# ButtonBoard.net
KiCad netlist of a schematic drawn in EAGLE
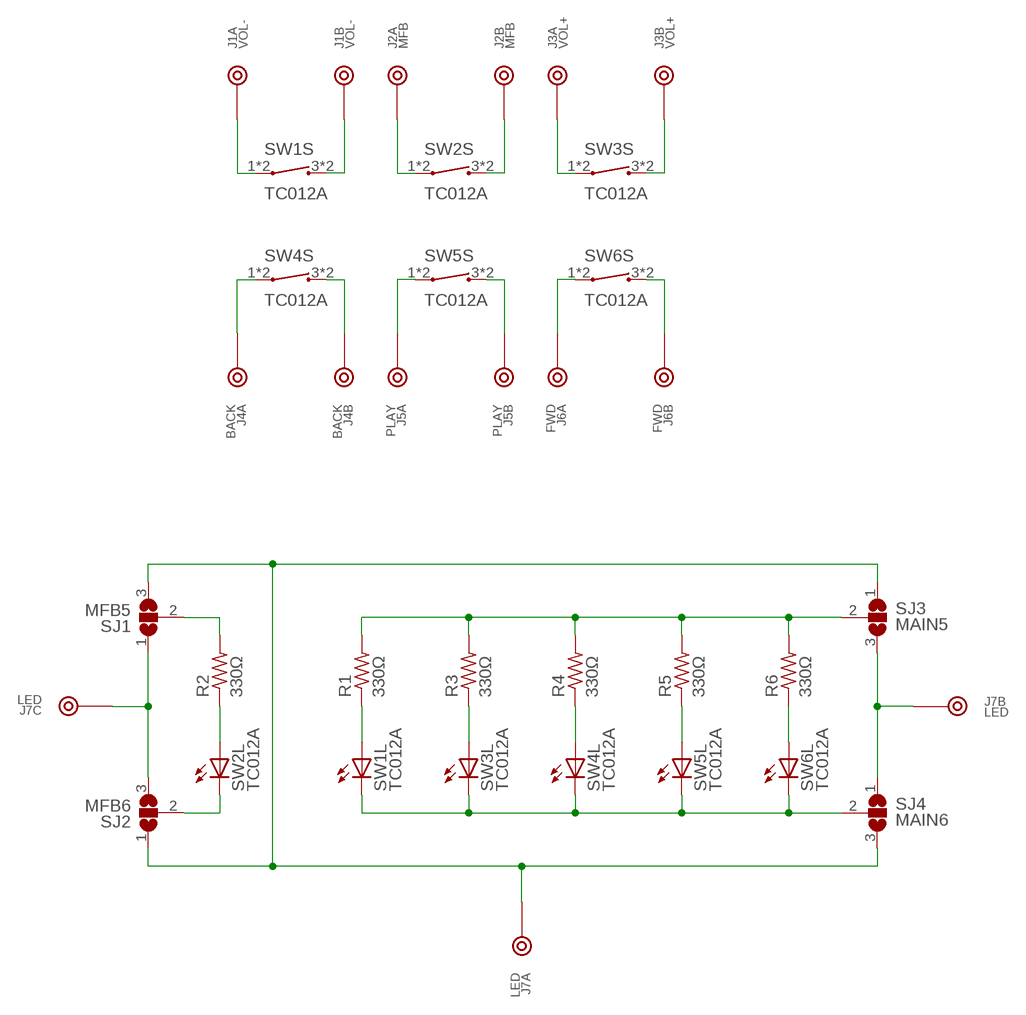
[diagram p0: schematic, sheet 1]

(export (version "E")
  (design (tool "Eeschema 10.0.6"))
  (components
    (comp (ref "J1")
      (value "VOL-")
      (footprint "eagle-import:2PIN")
      (libsource (lib "eagle-import") (part "GEN-2PIN"))
    )
    (comp (ref "J2")
      (value "MFB")
      (footprint "eagle-import:2PIN")
      (libsource (lib "eagle-import") (part "GEN-2PIN"))
    )
    (comp (ref "J3")
      (value "VOL+")
      (footprint "eagle-import:2PIN")
      (libsource (lib "eagle-import") (part "GEN-2PIN"))
    )
    (comp (ref "J4")
      (value "BACK")
      (footprint "eagle-import:2PIN")
      (libsource (lib "eagle-import") (part "GEN-2PIN"))
    )
    (comp (ref "J5")
      (value "PLAY")
      (footprint "eagle-import:2PIN")
      (libsource (lib "eagle-import") (part "GEN-2PIN"))
    )
    (comp (ref "J6")
      (value "FWD")
      (footprint "eagle-import:2PIN")
      (libsource (lib "eagle-import") (part "GEN-2PIN"))
    )
    (comp (ref "J7")
      (value "LED")
      (footprint "eagle-import:3PIN")
      (libsource (lib "eagle-import") (part "GEN-3PIN"))
    )
    (comp (ref "R1")
      (value "330Ω")
      (footprint "eagle-import:R0805")
      (libsource (lib "eagle-import") (part "R-US_R0805"))
    )
    (comp (ref "R2")
      (value "330Ω")
      (footprint "eagle-import:R0805")
      (libsource (lib "eagle-import") (part "R-US_R0805"))
    )
    (comp (ref "R3")
      (value "330Ω")
      (footprint "eagle-import:R0805")
      (libsource (lib "eagle-import") (part "R-US_R0805"))
    )
    (comp (ref "R4")
      (value "330Ω")
      (footprint "eagle-import:R0805")
      (libsource (lib "eagle-import") (part "R-US_R0805"))
    )
    (comp (ref "R5")
      (value "330Ω")
      (footprint "eagle-import:R0805")
      (libsource (lib "eagle-import") (part "R-US_R0805"))
    )
    (comp (ref "R6")
      (value "330Ω")
      (footprint "eagle-import:R0805")
      (libsource (lib "eagle-import") (part "R-US_R0805"))
    )
    (comp (ref "SJ1")
      (value "MFB5")
      (footprint "eagle-import:SJ_2")
      (libsource (lib "eagle-import") (part "SJ2W"))
    )
    (comp (ref "SJ2")
      (value "MFB6")
      (footprint "eagle-import:SJ_2")
      (libsource (lib "eagle-import") (part "SJ2W"))
    )
    (comp (ref "SJ3")
      (value "MAIN5")
      (footprint "eagle-import:SJ_2")
      (libsource (lib "eagle-import") (part "SJ2W"))
    )
    (comp (ref "SJ4")
      (value "MAIN6")
      (footprint "eagle-import:SJ_2")
      (libsource (lib "eagle-import") (part "SJ2W"))
    )
    (comp (ref "SW1")
      (value "TC012A")
      (footprint "eagle-import:TC012A")
      (libsource (lib "eagle-import") (part "TC012A"))
    )
    (comp (ref "SW2")
      (value "TC012A")
      (footprint "eagle-import:TC012A")
      (libsource (lib "eagle-import") (part "TC012A"))
    )
    (comp (ref "SW3")
      (value "TC012A")
      (footprint "eagle-import:TC012A")
      (libsource (lib "eagle-import") (part "TC012A"))
    )
    (comp (ref "SW4")
      (value "TC012A")
      (footprint "eagle-import:TC012A")
      (libsource (lib "eagle-import") (part "TC012A"))
    )
    (comp (ref "SW5")
      (value "TC012A")
      (footprint "eagle-import:TC012A")
      (libsource (lib "eagle-import") (part "TC012A"))
    )
    (comp (ref "SW6")
      (value "TC012A")
      (footprint "eagle-import:TC012A")
      (libsource (lib "eagle-import") (part "TC012A"))
    )
  )
  (nets
    (net (code "1") (name "Net-(J1A-P$1)") (class "Default")
      (node (ref "J1") (pin "1") (pinfunction "P$1_1") (pintype "bidirectional"))
      (node (ref "SW1") (pin "1") (pinfunction "1_1") (pintype "passive"))
      (node (ref "SW1") (pin "2") (pinfunction "1_2") (pintype "passive"))
    )
    (net (code "2") (name "Net-(J1B-P$1)") (class "Default")
      (node (ref "J1") (pin "2") (pinfunction "P$1_2") (pintype "bidirectional"))
      (node (ref "SW1") (pin "3") (pinfunction "2_3") (pintype "passive"))
      (node (ref "SW1") (pin "4") (pinfunction "2_4") (pintype "passive"))
    )
    (net (code "3") (name "Net-(J2A-P$1)") (class "Default")
      (node (ref "J2") (pin "1") (pinfunction "P$1_1") (pintype "bidirectional"))
      (node (ref "SW2") (pin "1") (pinfunction "1_1") (pintype "passive"))
      (node (ref "SW2") (pin "2") (pinfunction "1_2") (pintype "passive"))
    )
    (net (code "4") (name "Net-(J2B-P$1)") (class "Default")
      (node (ref "J2") (pin "2") (pinfunction "P$1_2") (pintype "bidirectional"))
      (node (ref "SW2") (pin "3") (pinfunction "2_3") (pintype "passive"))
      (node (ref "SW2") (pin "4") (pinfunction "2_4") (pintype "passive"))
    )
    (net (code "5") (name "Net-(J3A-P$1)") (class "Default")
      (node (ref "J3") (pin "1") (pinfunction "P$1_1") (pintype "bidirectional"))
      (node (ref "SW3") (pin "1") (pinfunction "1_1") (pintype "passive"))
      (node (ref "SW3") (pin "2") (pinfunction "1_2") (pintype "passive"))
    )
    (net (code "6") (name "Net-(J3B-P$1)") (class "Default")
      (node (ref "J3") (pin "2") (pinfunction "P$1_2") (pintype "bidirectional"))
      (node (ref "SW3") (pin "3") (pinfunction "2_3") (pintype "passive"))
      (node (ref "SW3") (pin "4") (pinfunction "2_4") (pintype "passive"))
    )
    (net (code "7") (name "Net-(J4A-P$1)") (class "Default")
      (node (ref "J4") (pin "1") (pinfunction "P$1_1") (pintype "bidirectional"))
      (node (ref "SW4") (pin "1") (pinfunction "1_1") (pintype "passive"))
      (node (ref "SW4") (pin "2") (pinfunction "1_2") (pintype "passive"))
    )
    (net (code "8") (name "Net-(J4B-P$1)") (class "Default")
      (node (ref "J4") (pin "2") (pinfunction "P$1_2") (pintype "bidirectional"))
      (node (ref "SW4") (pin "3") (pinfunction "2_3") (pintype "passive"))
      (node (ref "SW4") (pin "4") (pinfunction "2_4") (pintype "passive"))
    )
    (net (code "9") (name "Net-(J5A-P$1)") (class "Default")
      (node (ref "J5") (pin "1") (pinfunction "P$1_1") (pintype "bidirectional"))
      (node (ref "SW5") (pin "1") (pinfunction "1_1") (pintype "passive"))
      (node (ref "SW5") (pin "2") (pinfunction "1_2") (pintype "passive"))
    )
    (net (code "10") (name "Net-(J5B-P$1)") (class "Default")
      (node (ref "J5") (pin "2") (pinfunction "P$1_2") (pintype "bidirectional"))
      (node (ref "SW5") (pin "3") (pinfunction "2_3") (pintype "passive"))
      (node (ref "SW5") (pin "4") (pinfunction "2_4") (pintype "passive"))
    )
    (net (code "11") (name "Net-(J6A-P$1)") (class "Default")
      (node (ref "J6") (pin "1") (pinfunction "P$1_1") (pintype "bidirectional"))
      (node (ref "SW6") (pin "1") (pinfunction "1_1") (pintype "passive"))
      (node (ref "SW6") (pin "2") (pinfunction "1_2") (pintype "passive"))
    )
    (net (code "12") (name "Net-(J6B-P$1)") (class "Default")
      (node (ref "J6") (pin "2") (pinfunction "P$1_2") (pintype "bidirectional"))
      (node (ref "SW6") (pin "3") (pinfunction "2_3") (pintype "passive"))
      (node (ref "SW6") (pin "4") (pinfunction "2_4") (pintype "passive"))
    )
    (net (code "13") (name "Net-(J7A-P$1)") (class "Default")
      (node (ref "J7") (pin "1") (pinfunction "P$1_1") (pintype "bidirectional"))
      (node (ref "SJ1") (pin "3") (pinfunction "3_3") (pintype "passive"))
      (node (ref "SJ2") (pin "1") (pinfunction "1_1") (pintype "passive"))
      (node (ref "SJ3") (pin "1") (pinfunction "1_1") (pintype "passive"))
      (node (ref "SJ4") (pin "3") (pinfunction "3_3") (pintype "passive"))
    )
    (net (code "14") (name "Net-(J7B-P$1)") (class "Default")
      (node (ref "J7") (pin "2") (pinfunction "P$1_2") (pintype "bidirectional"))
      (node (ref "SJ3") (pin "3") (pinfunction "3_3") (pintype "passive"))
      (node (ref "SJ4") (pin "1") (pinfunction "1_1") (pintype "passive"))
    )
    (net (code "15") (name "Net-(J7C-P$1)") (class "Default")
      (node (ref "J7") (pin "3") (pinfunction "P$1_3") (pintype "bidirectional"))
      (node (ref "SJ1") (pin "1") (pinfunction "1_1") (pintype "passive"))
      (node (ref "SJ2") (pin "3") (pinfunction "3_3") (pintype "passive"))
    )
    (net (code "16") (name "Net-(R1-Pad2)") (class "Default")
      (node (ref "R1") (pin "2") (pinfunction "2_2") (pintype "passive"))
      (node (ref "R3") (pin "2") (pinfunction "2_2") (pintype "passive"))
      (node (ref "R4") (pin "2") (pinfunction "2_2") (pintype "passive"))
      (node (ref "R5") (pin "2") (pinfunction "2_2") (pintype "passive"))
      (node (ref "R6") (pin "2") (pinfunction "2_2") (pintype "passive"))
      (node (ref "SJ3") (pin "2") (pinfunction "2_2") (pintype "passive"))
    )
    (net (code "17") (name "Net-(R2-Pad2)") (class "Default")
      (node (ref "R2") (pin "2") (pinfunction "2_2") (pintype "passive"))
      (node (ref "SJ1") (pin "2") (pinfunction "2_2") (pintype "passive"))
    )
    (net (code "18") (name "Net-(SW1A-A)") (class "Default")
      (node (ref "R1") (pin "1") (pinfunction "1_1") (pintype "passive"))
      (node (ref "SW1") (pin "5") (pinfunction "A_5") (pintype "passive"))
    )
    (net (code "19") (name "Net-(SW1A-C)") (class "Default")
      (node (ref "SJ4") (pin "2") (pinfunction "2_2") (pintype "passive"))
      (node (ref "SW1") (pin "6") (pinfunction "C_6") (pintype "passive"))
      (node (ref "SW3") (pin "6") (pinfunction "C_6") (pintype "passive"))
      (node (ref "SW4") (pin "6") (pinfunction "C_6") (pintype "passive"))
      (node (ref "SW5") (pin "6") (pinfunction "C_6") (pintype "passive"))
      (node (ref "SW6") (pin "6") (pinfunction "C_6") (pintype "passive"))
    )
    (net (code "20") (name "Net-(SW2A-A)") (class "Default")
      (node (ref "R2") (pin "1") (pinfunction "1_1") (pintype "passive"))
      (node (ref "SW2") (pin "5") (pinfunction "A_5") (pintype "passive"))
    )
    (net (code "21") (name "Net-(SW2A-C)") (class "Default")
      (node (ref "SJ2") (pin "2") (pinfunction "2_2") (pintype "passive"))
      (node (ref "SW2") (pin "6") (pinfunction "C_6") (pintype "passive"))
    )
    (net (code "22") (name "Net-(SW3A-A)") (class "Default")
      (node (ref "R3") (pin "1") (pinfunction "1_1") (pintype "passive"))
      (node (ref "SW3") (pin "5") (pinfunction "A_5") (pintype "passive"))
    )
    (net (code "23") (name "Net-(SW4A-A)") (class "Default")
      (node (ref "R4") (pin "1") (pinfunction "1_1") (pintype "passive"))
      (node (ref "SW4") (pin "5") (pinfunction "A_5") (pintype "passive"))
    )
    (net (code "24") (name "Net-(SW5A-A)") (class "Default")
      (node (ref "R5") (pin "1") (pinfunction "1_1") (pintype "passive"))
      (node (ref "SW5") (pin "5") (pinfunction "A_5") (pintype "passive"))
    )
    (net (code "25") (name "Net-(SW6A-A)") (class "Default")
      (node (ref "R6") (pin "1") (pinfunction "1_1") (pintype "passive"))
      (node (ref "SW6") (pin "5") (pinfunction "A_5") (pintype "passive"))
    )
  )
)
